# USB_OTG_HS.net
KiCad netlist of a schematic drawn in Altium Designer
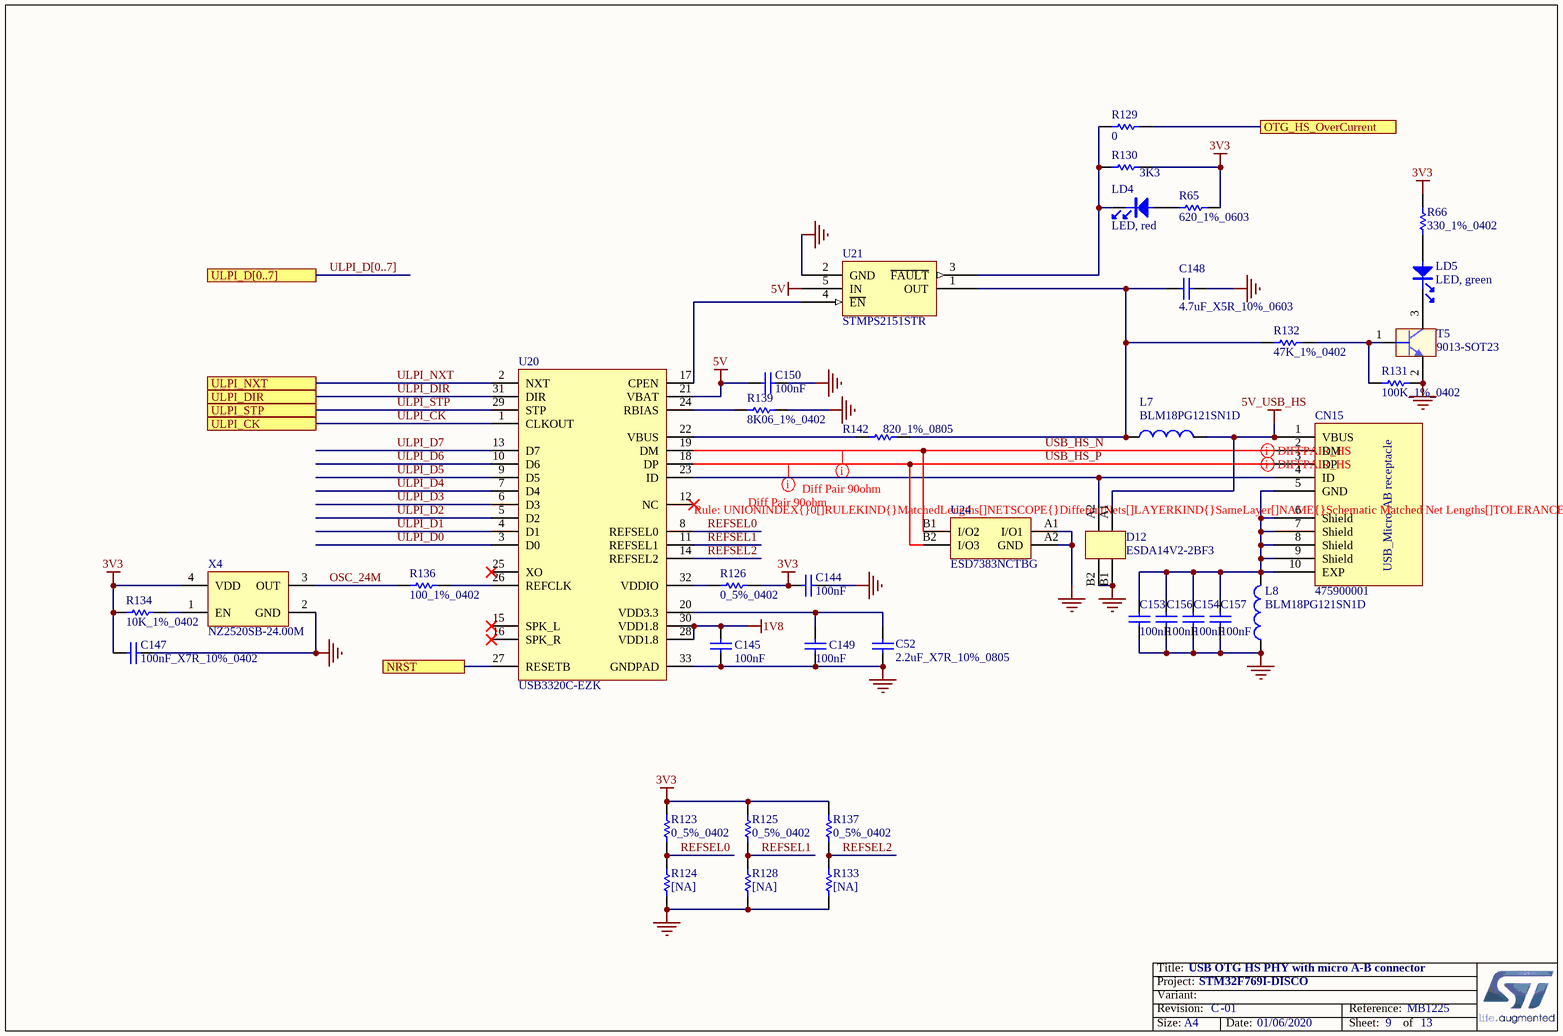
[diagram p0: USB_OTG_HS.SchDoc]

(export (version "E")
  (design (tool "Eeschema 10.0.6"))
  (components
    (comp (ref "C52")
      (value "2.2uF_X7R_10%_0805")
      (footprint "TAN-A")
      (description "Capacitor,2.2uF,16V, X7R,10%,0805,YAGEO")
      (libsource (lib "MCD_TOOLS") (part "Cap_2.2uF_X7R_10%_0805"))
    )
    (comp (ref "C144")
      (value "100nF")
      (footprint "0402C")
      (description "Capacitor,100nF,16V,X7R,10%,0402,YAGEO")
      (libsource (lib "MCD_TOOLS") (part "Cap_100nF_X7R_10%_0402"))
    )
    (comp (ref "C145")
      (value "100nF")
      (footprint "0402C")
      (description "Capacitor,100nF,16V,X7R,10%,0402,YAGEO")
      (libsource (lib "MCD_TOOLS") (part "Cap_100nF_X7R_10%_0402"))
    )
    (comp (ref "C147")
      (value "100nF_X7R_10%_0402")
      (footprint "0402C")
      (description "Capacitor,100nF,16V,X7R,10%,0402,YAGEO")
      (libsource (lib "MCD_TOOLS_CAPACITOR") (part "Cap_100nF_X7R_10%_0402"))
    )
    (comp (ref "C148")
      (value "4.7uF_X5R_10%_0603")
      (footprint "0603C")
      (description "Capacitor,4.7uF,16V, X5R,10%,0603,YAGEO")
      (libsource (lib "MCD_TOOLS") (part "Cap_4.7uF_X5R_10%_0603"))
    )
    (comp (ref "C149")
      (value "100nF")
      (footprint "0402C")
      (description "Capacitor,100nF,16V,X7R,10%,0402,YAGEO")
      (libsource (lib "MCD_TOOLS") (part "Cap_100nF_X7R_10%_0402"))
    )
    (comp (ref "C150")
      (value "100nF")
      (footprint "0402C")
      (description "Capacitor,100nF,16V,X7R,10%,0402,YAGEO")
      (libsource (lib "MCD_TOOLS") (part "Cap_100nF_X7R_10%_0402"))
    )
    (comp (ref "C153")
      (value "100nF")
      (footprint "0402C")
      (description "Capacitor,100nF,16V,X7R,10%,0402,YAGEO")
      (libsource (lib "MCD_TOOLS") (part "Cap_100nF_X7R_10%_0402"))
    )
    (comp (ref "C154")
      (value "100nF")
      (footprint "0402C")
      (description "Capacitor,100nF,16V,X7R,10%,0402,YAGEO")
      (libsource (lib "MCD_TOOLS") (part "Cap_100nF_X7R_10%_0402"))
    )
    (comp (ref "C156")
      (value "100nF")
      (footprint "0402C")
      (description "Capacitor,100nF,16V,X7R,10%,0402,YAGEO")
      (libsource (lib "MCD_TOOLS") (part "Cap_100nF_X7R_10%_0402"))
    )
    (comp (ref "C157")
      (value "100nF")
      (footprint "0402C")
      (description "Capacitor,100nF,16V,X7R,10%,0402,YAGEO")
      (libsource (lib "MCD_TOOLS") (part "Cap_100nF_X7R_10%_0402"))
    )
    (comp (ref "CN15")
      (value "475900001")
      (footprint "MOLEX_47590001")
      (description "USB-MICRO-AB, 47590-0001, SMT, MOLEX")
      (libsource (lib "MCD_TOOLS") (part "475900001"))
    )
    (comp (ref "D12")
      (value "ESDA14V2-2BF3")
      (footprint "BGA4_0R4_0R8X0R8")
      (description "Quad bidirectional Transil array for ESD protection")
      (libsource (lib "MCD_TOOLS_MISCELLANEOUS") (part "ESDA14V2-2BF3"))
    )
    (comp (ref "L7")
      (value "BLM18PG121SN1D")
      (footprint "0603L")
      (description "Bead,120R,2A,0603,BLM18PG121SN1D,MURATA")
      (libsource (lib "MCD_TOOLS") (part "BEAD_120R_2A_0603"))
    )
    (comp (ref "L8")
      (value "BLM18PG121SN1D")
      (footprint "0603L")
      (description "Bead,120R,2A,0603,BLM18PG121SN1D,MURATA")
      (libsource (lib "MCD_TOOLS") (part "BEAD_120R_2A_0603"))
    )
    (comp (ref "LD4")
      (value "LED, red")
      (footprint "0603D")
      (description "LED, red, 0603")
      (libsource (lib "MCD_TOOLS") (part "LED_red"))
    )
    (comp (ref "LD5")
      (value "LED, green")
      (footprint "0603D")
      (description "LED, green, 0603")
      (libsource (lib "MCD_TOOLS") (part "LED_green"))
    )
    (comp (ref "R65")
      (value "620_1%_0603")
      (footprint "0603R")
      (description "Resistor,620,0603,1%,VISHAY")
      (libsource (lib "MCD_TOOLS") (part "Res_620_1%_0603"))
    )
    (comp (ref "R66")
      (value "330_1%_0402")
      (footprint "0402R")
      (description "Resistor,330,0402,1%,YAGEO")
      (libsource (lib "MCD_TOOLS") (part "Res_330_1%_0402"))
    )
    (comp (ref "R123")
      (value "0_5%_0402")
      (footprint "0402R")
      (description "Resistor,0,0402,5%,YAGEO")
      (libsource (lib "MCD_TOOLS") (part "Res_0_5%_0402"))
    )
    (comp (ref "R124")
      (value "[NA]")
      (footprint "0402R")
      (description "Resistor,[NA],0402")
      (libsource (lib "MCD_TOOLS") (part "Res_NA_0402"))
    )
    (comp (ref "R125")
      (value "0_5%_0402")
      (footprint "0402R")
      (description "Resistor,0,0402,5%,YAGEO")
      (libsource (lib "MCD_TOOLS") (part "Res_0_5%_0402"))
    )
    (comp (ref "R126")
      (value "0_5%_0402")
      (footprint "0402R")
      (description "Resistor,0,0402,5%,YAGEO")
      (libsource (lib "MCD_TOOLS") (part "Res_0_5%_0402"))
    )
    (comp (ref "R128")
      (value "[NA]")
      (footprint "0402R")
      (description "Resistor,[NA],0402")
      (libsource (lib "MCD_TOOLS") (part "Res_NA_0402"))
    )
    (comp (ref "R129")
      (value "0")
      (footprint "0402R")
      (description "Resistor,0,0402,5%,YAGEO")
      (libsource (lib "MCD_TOOLS") (part "Res_0_5%_0402"))
    )
    (comp (ref "R130")
      (value "3K3")
      (footprint "0402R")
      (description "Resistor,3K3,0402,1%,YAGEO")
      (libsource (lib "MCD_TOOLS") (part "Res_3K3_1%_0402"))
    )
    (comp (ref "R131")
      (value "100K_1%_0402")
      (footprint "0402R")
      (description "Resistor,100K,0402,1%,YAGEO")
      (libsource (lib "MCD_TOOLS_RESISTOR") (part "Res_100K_1%_0402"))
    )
    (comp (ref "R132")
      (value "47K_1%_0402")
      (footprint "0402R")
      (description "Resistor,47K,0402,1%,YAGEO")
      (libsource (lib "MCD_TOOLS") (part "Res_47K_1%_0402"))
    )
    (comp (ref "R133")
      (value "[NA]")
      (footprint "0402R")
      (description "Resistor,[NA],0402")
      (libsource (lib "MCD_TOOLS") (part "Res_NA_0402"))
    )
    (comp (ref "R134")
      (value "10K_1%_0402")
      (footprint "0402R")
      (description "Resistor,10K,0402,1%,YAGEO")
      (libsource (lib "MCD_TOOLS") (part "Res_10K_1%_0402"))
    )
    (comp (ref "R136")
      (value "100_1%_0402")
      (footprint "0402R")
      (description "Resistor,100,0402,1%,YAGEO")
      (libsource (lib "MCD_TOOLS") (part "Res_100_1%_0402"))
    )
    (comp (ref "R137")
      (value "0_5%_0402")
      (footprint "0402R")
      (description "Resistor,0,0402,5%,YAGEO")
      (libsource (lib "MCD_TOOLS") (part "Res_0_5%_0402"))
    )
    (comp (ref "R139")
      (value "8K06_1%_0402")
      (footprint "0402R")
      (description "Resistor,8K06,0402,1%,YAGEO")
      (libsource (lib "MCD_TOOLS") (part "Res_8K06_1%_0402"))
    )
    (comp (ref "R142")
      (value "820_1%_0805")
      (footprint "0805R")
      (description "Resistor,820,0805,1%,YAGEO")
      (libsource (lib "MCD_TOOLS") (part "Res_820_1%_0805"))
    )
    (comp (ref "T5")
      (value "9013-SOT23")
      (footprint "SOT-23")
      (description "NPN Bipolar Transistor")
      (libsource (lib "MCD_TOOLS_MISCELLANEOUS") (part "9013-SOT23"))
    )
    (comp (ref "U20")
      (value "USB3320C-EZK")
      (footprint "QFN32_0R5_5X5")
      (description "USB3320C,  Hi-Speed USB Host, Device or OTG PHY with ULPI Low Pin Interface")
      (fields (field (name "PROVIDED") "Sub Co"))
      (libsource (lib "MCD_TOOLS_MISCELLANEOUS") (part "USB3320C-EZK"))
    )
    (comp (ref "U21")
      (value "STMPS2151STR")
      (footprint "SOT23-5")
      (description "Enhanced single channel power switches")
      (libsource (lib "MCD_TOOLS_MISCELLANEOUS") (part "STMPS2151STR"))
    )
    (comp (ref "U24")
      (value "ESD7383NCTBG")
      (footprint "ESD_WLCSP4_CASE-567CB_0P80X0P80_P040")
      (description "Diode, 3-line low capacitance protection for high speed USB")
      (fields
        (field (name "INTERNAL_PART_NUMBER") "MCD-01979")
        (field (name "MANUFACTURER") "ON SEMICONDUCTOR")
        (field (name "PROVIDED_BY") "SUBCO")
      )
      (libsource (lib "MCD_PARTS_database") (part "ESD7383NCTBG"))
    )
    (comp (ref "X4")
      (value "NZ2520SB-24.00M")
      (footprint "OSC_4SM_2R5X2")
      (description "Oscillator 24.00Mhz, -+50PPM, 3.3V, Temp -55 to +125°C")
      (libsource (lib "MCD_TOOLS_MISCELLANEOUS") (part "OSC_24M_NZ2520SB"))
    )
  )
  (nets
    (net (code "1") (name "/NRST") (class "Default")
      (node (ref "U20") (pin "27") (pinfunction "RESETB_27") (pintype "passive"))
    )
    (net (code "2") (name "/OSC_24M") (class "Default")
      (node (ref "R136") (pin "1") (pinfunction "1_1") (pintype "passive"))
      (node (ref "X4") (pin "3") (pinfunction "OUT_3") (pintype "passive"))
    )
    (net (code "3") (name "/OTG_HS_OverCurrent") (class "Default")
      (node (ref "R129") (pin "2") (pinfunction "2_2") (pintype "passive"))
    )
    (net (code "4") (name "/REFSEL0") (class "Default")
      (node (ref "R123") (pin "1") (pinfunction "1_1") (pintype "passive"))
      (node (ref "R124") (pin "2") (pinfunction "2_2") (pintype "passive"))
      (node (ref "U20") (pin "8") (pinfunction "REFSEL0_8") (pintype "passive"))
    )
    (net (code "5") (name "/REFSEL1") (class "Default")
      (node (ref "R125") (pin "1") (pinfunction "1_1") (pintype "passive"))
      (node (ref "R128") (pin "2") (pinfunction "2_2") (pintype "passive"))
      (node (ref "U20") (pin "11") (pinfunction "REFSEL1_11") (pintype "passive"))
    )
    (net (code "6") (name "/REFSEL2") (class "Default")
      (node (ref "R133") (pin "2") (pinfunction "2_2") (pintype "passive"))
      (node (ref "R137") (pin "1") (pinfunction "1_1") (pintype "passive"))
      (node (ref "U20") (pin "14") (pinfunction "REFSEL2_14") (pintype "passive"))
    )
    (net (code "7") (name "/ULPI_CK") (class "Default")
      (node (ref "U20") (pin "1") (pinfunction "CLKOUT_1") (pintype "passive"))
    )
    (net (code "8") (name "/ULPI_D0") (class "Default")
      (node (ref "U20") (pin "3") (pinfunction "D0_3") (pintype "passive"))
    )
    (net (code "9") (name "/ULPI_D1") (class "Default")
      (node (ref "U20") (pin "4") (pinfunction "D1_4") (pintype "passive"))
    )
    (net (code "10") (name "/ULPI_D2") (class "Default")
      (node (ref "U20") (pin "5") (pinfunction "D2_5") (pintype "passive"))
    )
    (net (code "11") (name "/ULPI_D3") (class "Default")
      (node (ref "U20") (pin "6") (pinfunction "D3_6") (pintype "passive"))
    )
    (net (code "12") (name "/ULPI_D4") (class "Default")
      (node (ref "U20") (pin "7") (pinfunction "D4_7") (pintype "passive"))
    )
    (net (code "13") (name "/ULPI_D5") (class "Default")
      (node (ref "U20") (pin "9") (pinfunction "D5_9") (pintype "passive"))
    )
    (net (code "14") (name "/ULPI_D6") (class "Default")
      (node (ref "U20") (pin "10") (pinfunction "D6_10") (pintype "passive"))
    )
    (net (code "15") (name "/ULPI_D7") (class "Default")
      (node (ref "U20") (pin "13") (pinfunction "D7_13") (pintype "passive"))
    )
    (net (code "16") (name "/ULPI_DIR") (class "Default")
      (node (ref "U20") (pin "31") (pinfunction "DIR_31") (pintype "passive"))
    )
    (net (code "18") (name "/ULPI_NXT") (class "Default")
      (node (ref "U20") (pin "2") (pinfunction "NXT_2") (pintype "passive"))
    )
    (net (code "19") (name "/ULPI_STP") (class "Default")
      (node (ref "U20") (pin "29") (pinfunction "STP_29") (pintype "passive"))
    )
    (net (code "20") (name "/USB_HS_N") (class "Default")
      (node (ref "CN15") (pin "2") (pinfunction "DM_2") (pintype "passive"))
      (node (ref "U20") (pin "19") (pinfunction "DM_19") (pintype "passive"))
      (node (ref "U24") (pin "B1") (pinfunction "I/O2_B1") (pintype "passive"))
    )
    (net (code "21") (name "/USB_HS_P") (class "Default")
      (node (ref "CN15") (pin "3") (pinfunction "DP_3") (pintype "passive"))
      (node (ref "U20") (pin "18") (pinfunction "DP_18") (pintype "passive"))
      (node (ref "U24") (pin "B2") (pinfunction "I/O3_B2") (pintype "passive"))
    )
    (net (code "22") (name "1V8") (class "Default")
      (node (ref "C145") (pin "2") (pinfunction "2_2") (pintype "passive"))
      (node (ref "U20") (pin "28") (pinfunction "VDD1.8_28") (pintype "passive"))
      (node (ref "U20") (pin "30") (pinfunction "VDD1.8_30") (pintype "passive"))
    )
    (net (code "23") (name "3V3") (class "Default")
      (node (ref "C144") (pin "1") (pinfunction "1_1") (pintype "passive"))
      (node (ref "C147") (pin "1") (pinfunction "1_1") (pintype "passive"))
      (node (ref "R123") (pin "2") (pinfunction "2_2") (pintype "passive"))
      (node (ref "R125") (pin "2") (pinfunction "2_2") (pintype "passive"))
      (node (ref "R126") (pin "2") (pinfunction "2_2") (pintype "passive"))
      (node (ref "R130") (pin "1") (pinfunction "1_1") (pintype "passive"))
      (node (ref "R134") (pin "1") (pinfunction "1_1") (pintype "passive"))
      (node (ref "R137") (pin "2") (pinfunction "2_2") (pintype "passive"))
      (node (ref "R65") (pin "2") (pinfunction "2_2") (pintype "passive"))
      (node (ref "R66") (pin "2") (pinfunction "2_2") (pintype "passive"))
      (node (ref "X4") (pin "4") (pinfunction "VDD_4") (pintype "passive"))
    )
    (net (code "24") (name "5V") (class "Default")
      (node (ref "C150") (pin "1") (pinfunction "1_1") (pintype "passive"))
      (node (ref "U20") (pin "21") (pinfunction "VBAT_21") (pintype "passive"))
      (node (ref "U21") (pin "5") (pinfunction "IN_5") (pintype "passive"))
    )
    (net (code "25") (name "5V_USB_HS") (class "Default")
      (node (ref "CN15") (pin "1") (pinfunction "VBUS_1") (pintype "passive"))
      (node (ref "D12") (pin "A1") (pintype "passive"))
      (node (ref "L7") (pin "2") (pinfunction "2_2") (pintype "passive"))
    )
    (net (code "26") (name "GND") (class "Default")
      (node (ref "C144") (pin "2") (pinfunction "2_2") (pintype "passive"))
      (node (ref "C145") (pin "1") (pinfunction "1_1") (pintype "passive"))
      (node (ref "C147") (pin "2") (pinfunction "2_2") (pintype "passive"))
      (node (ref "C148") (pin "2") (pinfunction "2_2") (pintype "passive"))
      (node (ref "C149") (pin "1") (pinfunction "1_1") (pintype "passive"))
      (node (ref "C150") (pin "2") (pinfunction "2_2") (pintype "passive"))
      (node (ref "C153") (pin "1") (pinfunction "1_1") (pintype "passive"))
      (node (ref "C154") (pin "1") (pinfunction "1_1") (pintype "passive"))
      (node (ref "C156") (pin "1") (pinfunction "1_1") (pintype "passive"))
      (node (ref "C157") (pin "1") (pinfunction "1_1") (pintype "passive"))
      (node (ref "C52") (pin "1") (pinfunction "1_1") (pintype "passive"))
      (node (ref "D12") (pin "B1") (pintype "passive"))
      (node (ref "D12") (pin "B2") (pintype "passive"))
      (node (ref "L8") (pin "1") (pinfunction "1_1") (pintype "passive"))
      (node (ref "R124") (pin "1") (pinfunction "1_1") (pintype "passive"))
      (node (ref "R128") (pin "1") (pinfunction "1_1") (pintype "passive"))
      (node (ref "R131") (pin "2") (pinfunction "2_2") (pintype "passive"))
      (node (ref "R133") (pin "1") (pinfunction "1_1") (pintype "passive"))
      (node (ref "R139") (pin "2") (pinfunction "2_2") (pintype "passive"))
      (node (ref "T5") (pin "2") (pinfunction "E_2") (pintype "passive"))
      (node (ref "U20") (pin "33") (pinfunction "GNDPAD_33") (pintype "passive"))
      (node (ref "U21") (pin "2") (pinfunction "GND_2") (pintype "passive"))
      (node (ref "U24") (pin "A1") (pinfunction "I/O1_A1") (pintype "passive"))
      (node (ref "U24") (pin "A2") (pinfunction "GND_A2") (pintype "passive"))
      (node (ref "X4") (pin "2") (pinfunction "GND_2") (pintype "passive"))
    )
    (net (code "27") (name "Net-(CN15-EXP)") (class "Default")
      (node (ref "C153") (pin "2") (pinfunction "2_2") (pintype "passive"))
      (node (ref "C154") (pin "2") (pinfunction "2_2") (pintype "passive"))
      (node (ref "C156") (pin "2") (pinfunction "2_2") (pintype "passive"))
      (node (ref "C157") (pin "2") (pinfunction "2_2") (pintype "passive"))
      (node (ref "CN15") (pin "10") (pinfunction "EXP_10") (pintype "passive"))
      (node (ref "CN15") (pin "5") (pinfunction "GND_5") (pintype "passive"))
      (node (ref "CN15") (pin "6") (pinfunction "Shield_6") (pintype "passive"))
      (node (ref "CN15") (pin "7") (pinfunction "Shield_7") (pintype "passive"))
      (node (ref "CN15") (pin "8") (pinfunction "Shield_8") (pintype "passive"))
      (node (ref "CN15") (pin "9") (pinfunction "Shield_9") (pintype "passive"))
      (node (ref "L8") (pin "2") (pinfunction "2_2") (pintype "passive"))
    )
    (net (code "28") (name "Net-(CN15-ID)") (class "Default")
      (node (ref "CN15") (pin "4") (pinfunction "ID_4") (pintype "passive"))
      (node (ref "D12") (pin "A2") (pintype "passive"))
      (node (ref "U20") (pin "23") (pinfunction "ID_23") (pintype "passive"))
    )
    (net (code "29") (name "Net-(LD4-Pad1)") (class "Default")
      (node (ref "LD4") (pin "1") (pintype "passive"))
      (node (ref "R65") (pin "1") (pinfunction "1_1") (pintype "passive"))
    )
    (net (code "30") (name "Net-(LD5-Pad1)") (class "Default")
      (node (ref "LD5") (pin "1") (pintype "passive"))
      (node (ref "R66") (pin "1") (pinfunction "1_1") (pintype "passive"))
    )
    (net (code "31") (name "Net-(T5-B)") (class "Default")
      (node (ref "R131") (pin "1") (pinfunction "1_1") (pintype "passive"))
      (node (ref "R132") (pin "2") (pinfunction "2_2") (pintype "passive"))
      (node (ref "T5") (pin "1") (pinfunction "B_1") (pintype "passive"))
    )
    (net (code "32") (name "Net-(T5-C)") (class "Default")
      (node (ref "LD5") (pin "2") (pintype "passive"))
      (node (ref "T5") (pin "3") (pinfunction "C_3") (pintype "passive"))
    )
    (net (code "33") (name "Net-(U20-CPEN)") (class "Default")
      (node (ref "U20") (pin "17") (pinfunction "CPEN_17") (pintype "passive"))
      (node (ref "U21") (pin "4") (pinfunction "~{EN}_4") (pintype "input"))
    )
    (net (code "34") (name "Net-(U20-RBIAS)") (class "Default")
      (node (ref "R139") (pin "1") (pinfunction "1_1") (pintype "passive"))
      (node (ref "U20") (pin "24") (pinfunction "RBIAS_24") (pintype "passive"))
    )
    (net (code "35") (name "Net-(U20-REFCLK)") (class "Default")
      (node (ref "R136") (pin "2") (pinfunction "2_2") (pintype "passive"))
      (node (ref "U20") (pin "26") (pinfunction "REFCLK_26") (pintype "passive"))
    )
    (net (code "36") (name "Net-(U20-VBUS)") (class "Default")
      (node (ref "R142") (pin "1") (pinfunction "1_1") (pintype "passive"))
      (node (ref "U20") (pin "22") (pinfunction "VBUS_22") (pintype "passive"))
    )
    (net (code "37") (name "Net-(U20-VDD3.3)") (class "Default")
      (node (ref "C149") (pin "2") (pinfunction "2_2") (pintype "passive"))
      (node (ref "C52") (pin "2") (pinfunction "2_2") (pintype "passive"))
      (node (ref "U20") (pin "20") (pinfunction "VDD3.3_20") (pintype "passive"))
    )
    (net (code "38") (name "Net-(U20-VDDIO)") (class "Default")
      (node (ref "R126") (pin "1") (pinfunction "1_1") (pintype "passive"))
      (node (ref "U20") (pin "32") (pinfunction "VDDIO_32") (pintype "passive"))
    )
    (net (code "39") (name "Net-(U21-OUT)") (class "Default")
      (node (ref "C148") (pin "1") (pinfunction "1_1") (pintype "passive"))
      (node (ref "L7") (pin "1") (pinfunction "1_1") (pintype "passive"))
      (node (ref "R132") (pin "1") (pinfunction "1_1") (pintype "passive"))
      (node (ref "R142") (pin "2") (pinfunction "2_2") (pintype "passive"))
      (node (ref "U21") (pin "1") (pinfunction "OUT_1") (pintype "passive"))
    )
    (net (code "40") (name "Net-(U21-~{FAULT})") (class "Default")
      (node (ref "LD4") (pin "2") (pintype "passive"))
      (node (ref "R129") (pin "1") (pinfunction "1_1") (pintype "passive"))
      (node (ref "R130") (pin "2") (pinfunction "2_2") (pintype "passive"))
      (node (ref "U21") (pin "3") (pinfunction "~{FAULT}_3") (pintype "output"))
    )
    (net (code "41") (name "Net-(X4-EN)") (class "Default")
      (node (ref "R134") (pin "2") (pinfunction "2_2") (pintype "passive"))
      (node (ref "X4") (pin "1") (pinfunction "EN_1") (pintype "passive"))
    )
    (net (code "42") (name "unconnected-(U20-NC-Pad12)") (class "Default")
      (node (ref "U20") (pin "12") (pinfunction "NC_12") (pintype "passive+no_connect"))
    )
    (net (code "43") (name "unconnected-(U20-SPK_L-Pad15)") (class "Default")
      (node (ref "U20") (pin "15") (pinfunction "SPK_L_15") (pintype "passive+no_connect"))
    )
    (net (code "44") (name "unconnected-(U20-SPK_R-Pad16)") (class "Default")
      (node (ref "U20") (pin "16") (pinfunction "SPK_R_16") (pintype "passive+no_connect"))
    )
    (net (code "45") (name "unconnected-(U20-XO-Pad25)") (class "Default")
      (node (ref "U20") (pin "25") (pinfunction "XO_25") (pintype "passive+no_connect"))
    )
  )
)
